# joysticks.net
KiCad netlist of a schematic drawn in Altium Designer
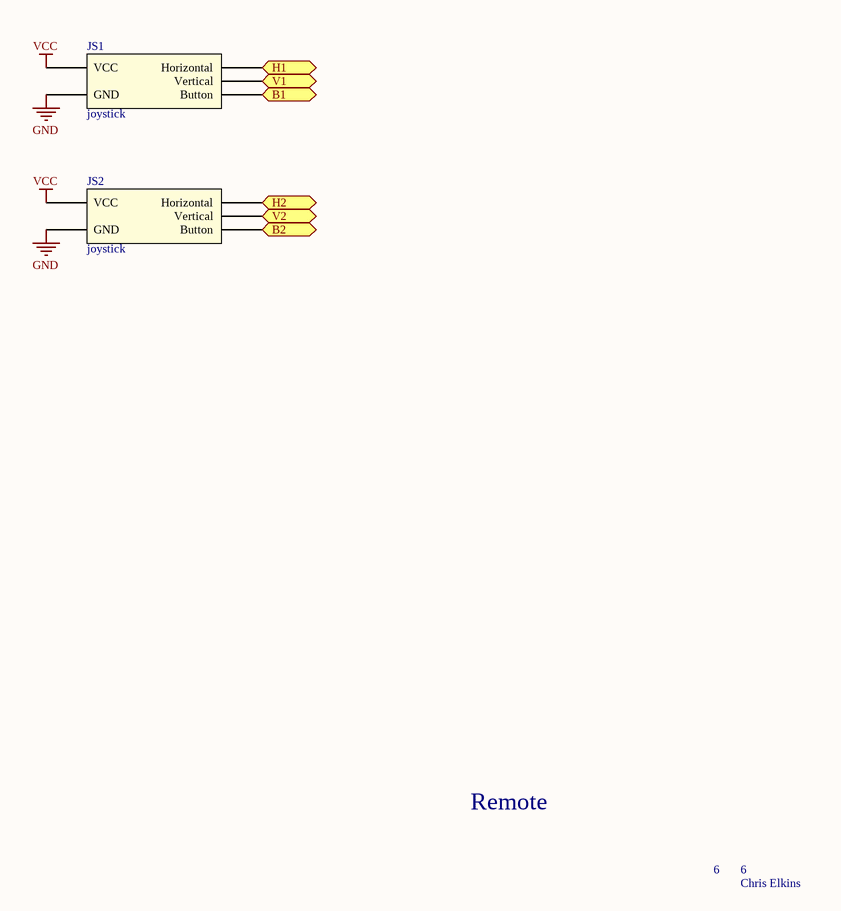
[diagram p0: joysticks.SchDoc]

(export (version "E")
  (design (tool "Eeschema 10.0.6"))
  (components
    (comp (ref "JS1")
      (value "joystick")
      (footprint "Joystick")
      (libsource (lib "Integrated_Library1") (part "joystick"))
    )
    (comp (ref "JS2")
      (value "joystick")
      (footprint "Joystick")
      (libsource (lib "Integrated_Library1") (part "joystick"))
    )
  )
  (nets
    (net (code "1") (name "/B1") (class "Default")
      (node (ref "JS1") (pin "B1A") (pinfunction "Button_B1A") (pintype "passive"))
    )
    (net (code "2") (name "/B2") (class "Default")
      (node (ref "JS2") (pin "B1A") (pinfunction "Button_B1A") (pintype "passive"))
    )
    (net (code "3") (name "/H1") (class "Default")
      (node (ref "JS1") (pin "H2") (pinfunction "Horizontal_H2") (pintype "passive"))
    )
    (net (code "4") (name "/H2") (class "Default")
      (node (ref "JS2") (pin "H2") (pinfunction "Horizontal_H2") (pintype "passive"))
    )
    (net (code "5") (name "/V1") (class "Default")
      (node (ref "JS1") (pin "V2") (pinfunction "Vertical_V2") (pintype "passive"))
    )
    (net (code "6") (name "/V2") (class "Default")
      (node (ref "JS2") (pin "V2") (pinfunction "Vertical_V2") (pintype "passive"))
    )
    (net (code "7") (name "GND") (class "Default")
      (node (ref "JS1") (pin "V3") (pinfunction "GND_V3") (pintype "passive"))
      (node (ref "JS2") (pin "V3") (pinfunction "GND_V3") (pintype "passive"))
    )
    (net (code "8") (name "VCC") (class "Default")
      (node (ref "JS1") (pin "V1") (pinfunction "VCC_V1") (pintype "passive"))
      (node (ref "JS2") (pin "V1") (pinfunction "VCC_V1") (pintype "passive"))
    )
  )
)
